# d_counter.net
KiCad netlist of a schematic drawn in EAGLE
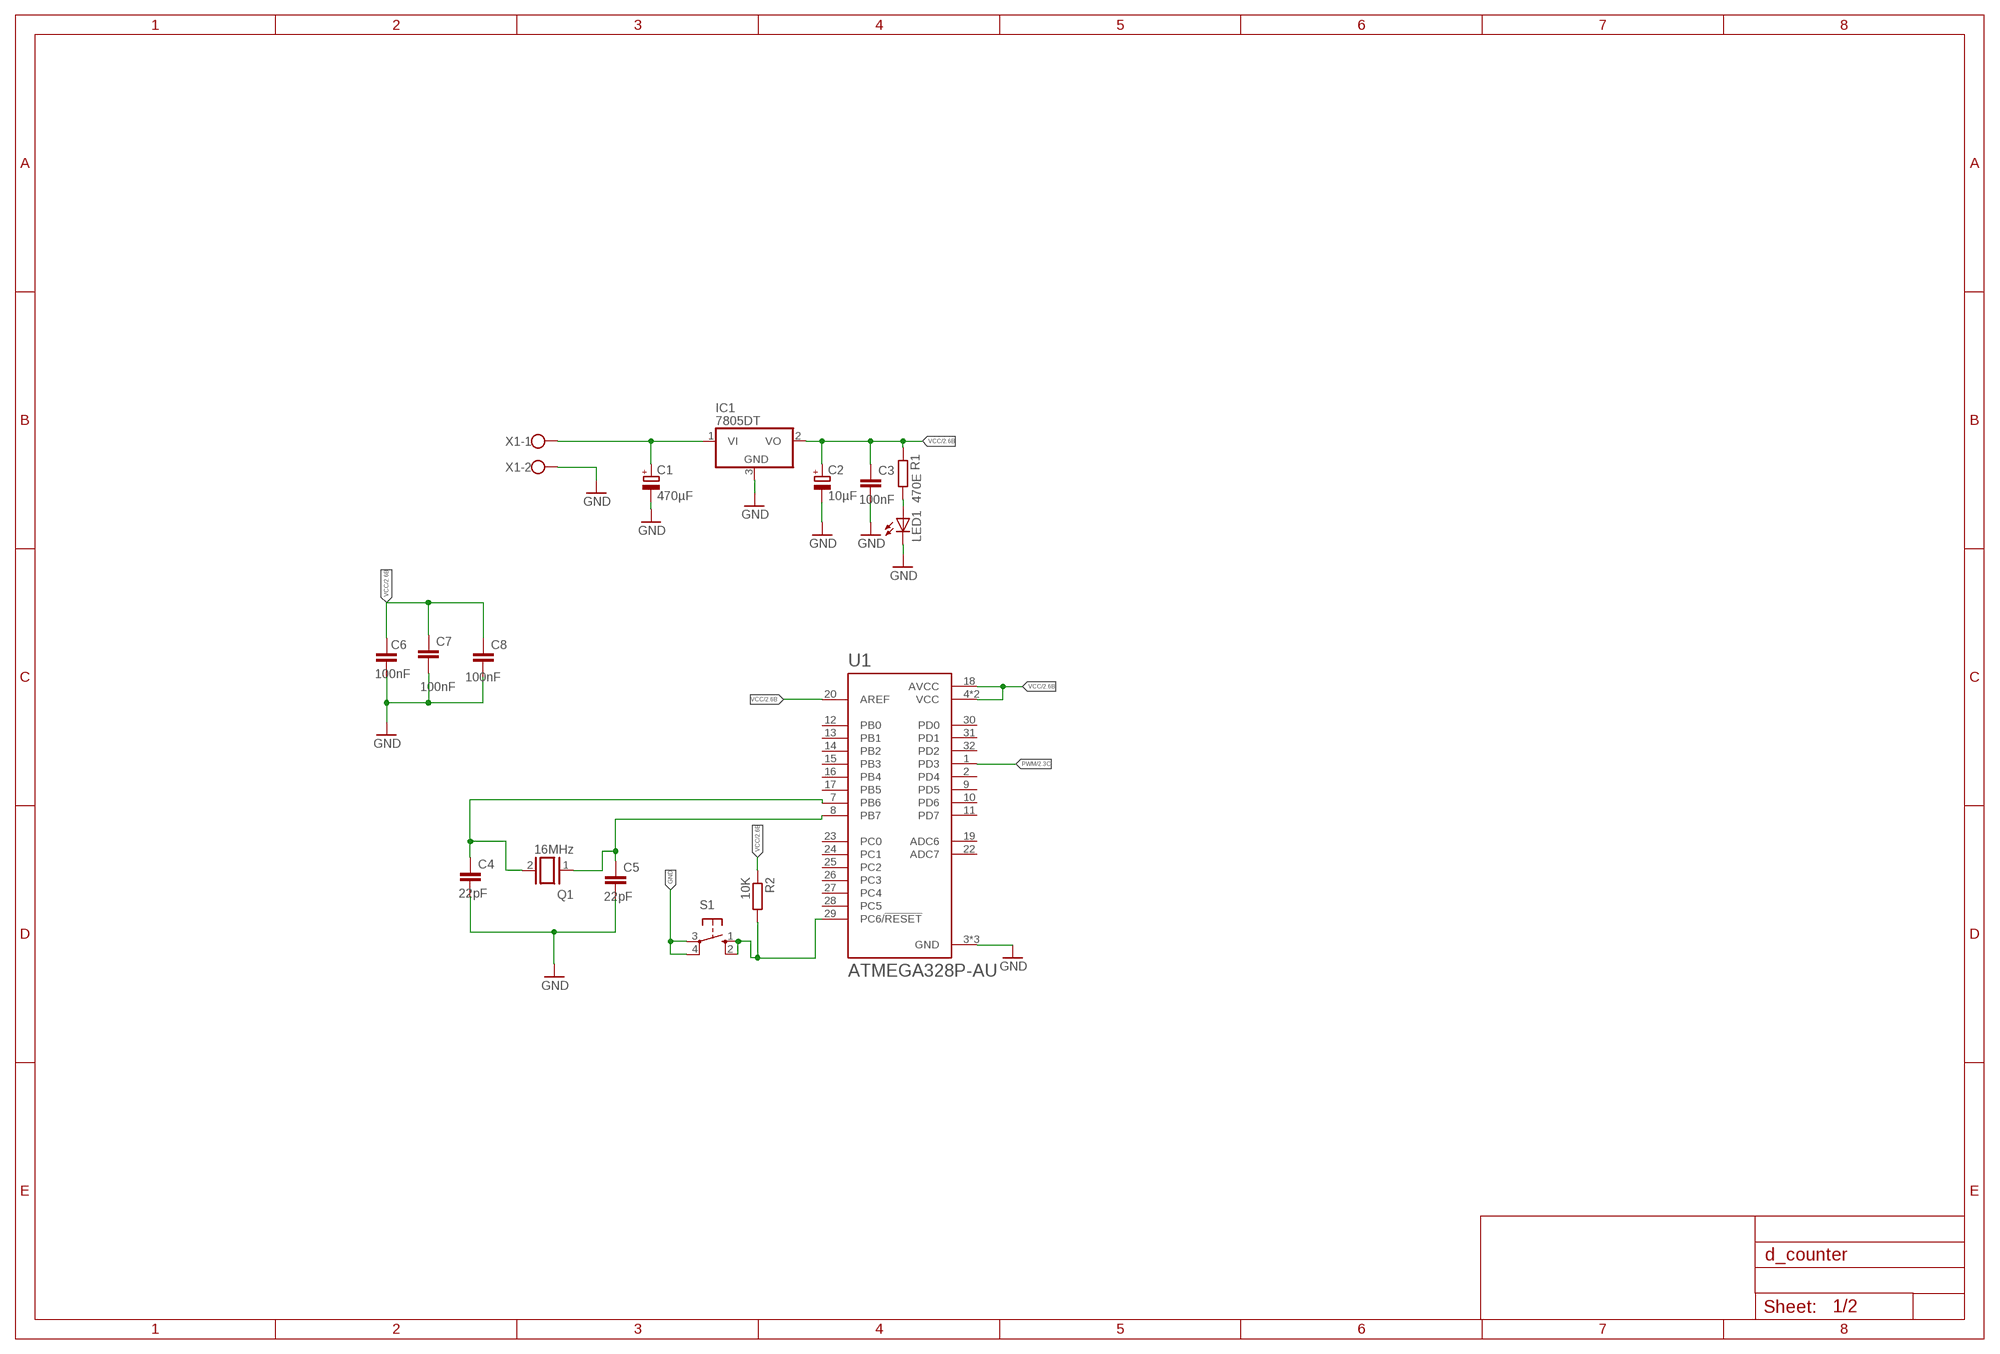
[diagram p0: schematic, sheet 1]
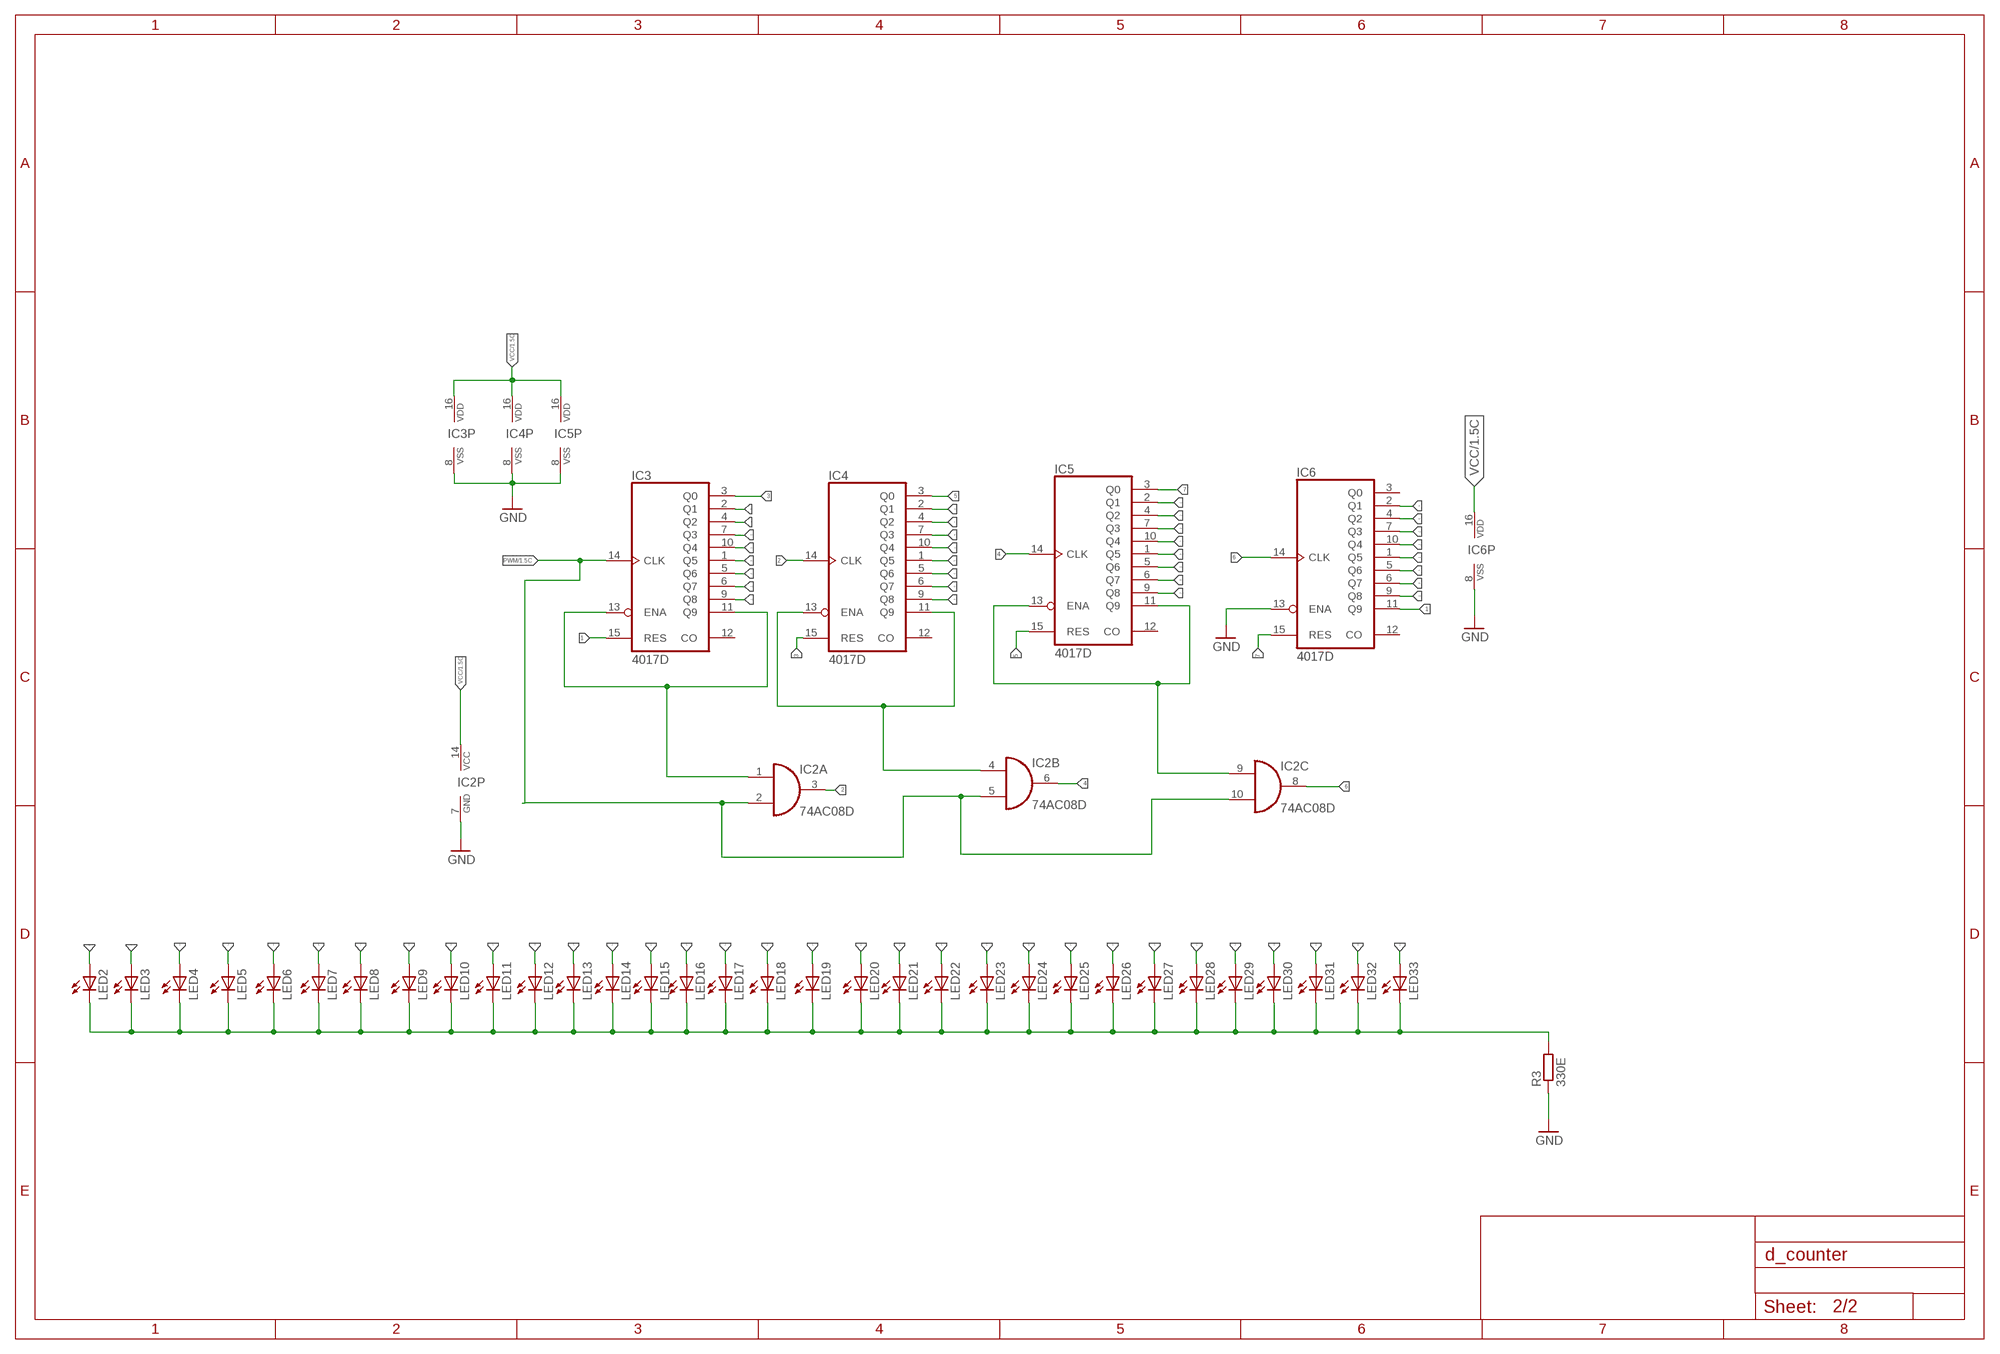
[diagram p1: schematic, sheet 2]

(export (version "E")
  (design (tool "Eeschema 10.0.6"))
  (components
    (comp (ref "IC2")
      (value "74AC08D")
      (footprint "eagle-import:SO14")
      (libsource (lib "eagle-import") (part "7408DAC"))
    )
    (comp (ref "IC3")
      (value "4017D")
      (footprint "eagle-import:SO16")
      (libsource (lib "eagle-import") (part "4017D"))
    )
    (comp (ref "IC4")
      (value "4017D")
      (footprint "eagle-import:SO16")
      (libsource (lib "eagle-import") (part "4017D"))
    )
    (comp (ref "IC5")
      (value "4017D")
      (footprint "eagle-import:SO16")
      (libsource (lib "eagle-import") (part "4017D"))
    )
    (comp (ref "IC6")
      (value "4017D")
      (footprint "eagle-import:SO16")
      (libsource (lib "eagle-import") (part "4017D"))
    )
    (comp (ref "LED2")
      (value "LEDSML1206")
      (footprint "eagle-import:SML1206")
      (libsource (lib "eagle-import") (part "LEDSML1206"))
    )
    (comp (ref "LED3")
      (value "LEDSML1206")
      (footprint "eagle-import:SML1206")
      (libsource (lib "eagle-import") (part "LEDSML1206"))
    )
    (comp (ref "LED4")
      (value "LEDSML1206")
      (footprint "eagle-import:SML1206")
      (libsource (lib "eagle-import") (part "LEDSML1206"))
    )
    (comp (ref "LED5")
      (value "LEDSML1206")
      (footprint "eagle-import:SML1206")
      (libsource (lib "eagle-import") (part "LEDSML1206"))
    )
    (comp (ref "LED6")
      (value "LEDSML1206")
      (footprint "eagle-import:SML1206")
      (libsource (lib "eagle-import") (part "LEDSML1206"))
    )
    (comp (ref "LED7")
      (value "LEDSML1206")
      (footprint "eagle-import:SML1206")
      (libsource (lib "eagle-import") (part "LEDSML1206"))
    )
    (comp (ref "LED8")
      (value "LEDSML1206")
      (footprint "eagle-import:SML1206")
      (libsource (lib "eagle-import") (part "LEDSML1206"))
    )
    (comp (ref "LED9")
      (value "LEDSML1206")
      (footprint "eagle-import:SML1206")
      (libsource (lib "eagle-import") (part "LEDSML1206"))
    )
    (comp (ref "LED10")
      (value "LEDSML1206")
      (footprint "eagle-import:SML1206")
      (libsource (lib "eagle-import") (part "LEDSML1206"))
    )
    (comp (ref "LED11")
      (value "LEDSML1206")
      (footprint "eagle-import:SML1206")
      (libsource (lib "eagle-import") (part "LEDSML1206"))
    )
    (comp (ref "LED12")
      (value "LEDSML1206")
      (footprint "eagle-import:SML1206")
      (libsource (lib "eagle-import") (part "LEDSML1206"))
    )
    (comp (ref "LED13")
      (value "LEDSML1206")
      (footprint "eagle-import:SML1206")
      (libsource (lib "eagle-import") (part "LEDSML1206"))
    )
    (comp (ref "LED14")
      (value "LEDSML1206")
      (footprint "eagle-import:SML1206")
      (libsource (lib "eagle-import") (part "LEDSML1206"))
    )
    (comp (ref "LED15")
      (value "LEDSML1206")
      (footprint "eagle-import:SML1206")
      (libsource (lib "eagle-import") (part "LEDSML1206"))
    )
    (comp (ref "LED16")
      (value "LEDSML1206")
      (footprint "eagle-import:SML1206")
      (libsource (lib "eagle-import") (part "LEDSML1206"))
    )
    (comp (ref "LED17")
      (value "LEDSML1206")
      (footprint "eagle-import:SML1206")
      (libsource (lib "eagle-import") (part "LEDSML1206"))
    )
    (comp (ref "LED18")
      (value "LEDSML1206")
      (footprint "eagle-import:SML1206")
      (libsource (lib "eagle-import") (part "LEDSML1206"))
    )
    (comp (ref "LED19")
      (value "LEDSML1206")
      (footprint "eagle-import:SML1206")
      (libsource (lib "eagle-import") (part "LEDSML1206"))
    )
    (comp (ref "LED20")
      (value "LEDSML1206")
      (footprint "eagle-import:SML1206")
      (libsource (lib "eagle-import") (part "LEDSML1206"))
    )
    (comp (ref "LED21")
      (value "LEDSML1206")
      (footprint "eagle-import:SML1206")
      (libsource (lib "eagle-import") (part "LEDSML1206"))
    )
    (comp (ref "LED22")
      (value "LEDSML1206")
      (footprint "eagle-import:SML1206")
      (libsource (lib "eagle-import") (part "LEDSML1206"))
    )
    (comp (ref "LED23")
      (value "LEDSML1206")
      (footprint "eagle-import:SML1206")
      (libsource (lib "eagle-import") (part "LEDSML1206"))
    )
    (comp (ref "LED24")
      (value "LEDSML1206")
      (footprint "eagle-import:SML1206")
      (libsource (lib "eagle-import") (part "LEDSML1206"))
    )
    (comp (ref "LED25")
      (value "LEDSML1206")
      (footprint "eagle-import:SML1206")
      (libsource (lib "eagle-import") (part "LEDSML1206"))
    )
    (comp (ref "LED26")
      (value "LEDSML1206")
      (footprint "eagle-import:SML1206")
      (libsource (lib "eagle-import") (part "LEDSML1206"))
    )
    (comp (ref "LED27")
      (value "LEDSML1206")
      (footprint "eagle-import:SML1206")
      (libsource (lib "eagle-import") (part "LEDSML1206"))
    )
    (comp (ref "LED28")
      (value "LEDSML1206")
      (footprint "eagle-import:SML1206")
      (libsource (lib "eagle-import") (part "LEDSML1206"))
    )
    (comp (ref "LED29")
      (value "LEDSML1206")
      (footprint "eagle-import:SML1206")
      (libsource (lib "eagle-import") (part "LEDSML1206"))
    )
    (comp (ref "LED30")
      (value "LEDSML1206")
      (footprint "eagle-import:SML1206")
      (libsource (lib "eagle-import") (part "LEDSML1206"))
    )
    (comp (ref "LED31")
      (value "LEDSML1206")
      (footprint "eagle-import:SML1206")
      (libsource (lib "eagle-import") (part "LEDSML1206"))
    )
    (comp (ref "LED32")
      (value "LEDSML1206")
      (footprint "eagle-import:SML1206")
      (libsource (lib "eagle-import") (part "LEDSML1206"))
    )
    (comp (ref "LED33")
      (value "LEDSML1206")
      (footprint "eagle-import:SML1206")
      (libsource (lib "eagle-import") (part "LEDSML1206"))
    )
    (comp (ref "R3")
      (value "330E")
      (footprint "eagle-import:R1206")
      (libsource (lib "eagle-import") (part "R-EU_R1206"))
    )
    (comp (ref "C1")
      (value "470µF")
      (footprint "eagle-import:150CLZ-1010")
      (libsource (lib "eagle-import") (part "CPOL-EU150CLZ-1010"))
    )
    (comp (ref "C2")
      (value "10µF")
      (footprint "eagle-import:150CLZ-1010")
      (libsource (lib "eagle-import") (part "CPOL-EU150CLZ-1010"))
    )
    (comp (ref "C3")
      (value "100nF")
      (footprint "eagle-import:C1206")
      (libsource (lib "eagle-import") (part "C-EUC1206"))
    )
    (comp (ref "C4")
      (value "22pF")
      (footprint "eagle-import:C1206")
      (libsource (lib "eagle-import") (part "C-EUC1206"))
    )
    (comp (ref "C5")
      (value "22pF")
      (footprint "eagle-import:C1206")
      (libsource (lib "eagle-import") (part "C-EUC1206"))
    )
    (comp (ref "C6")
      (value "100nF")
      (footprint "eagle-import:C1206")
      (libsource (lib "eagle-import") (part "C-EUC1206"))
    )
    (comp (ref "C7")
      (value "100nF")
      (footprint "eagle-import:C1206")
      (libsource (lib "eagle-import") (part "C-EUC1206"))
    )
    (comp (ref "C8")
      (value "100nF")
      (footprint "eagle-import:C1206")
      (libsource (lib "eagle-import") (part "C-EUC1206"))
    )
    (comp (ref "IC1")
      (value "7805DT")
      (footprint "eagle-import:TO252")
      (libsource (lib "eagle-import") (part "78DT05"))
    )
    (comp (ref "LED1")
      (value "LEDSMT1206")
      (footprint "eagle-import:1206")
      (libsource (lib "eagle-import") (part "LEDSMT1206"))
    )
    (comp (ref "Q1")
      (value "16MHz")
      (footprint "eagle-import:QS")
      (libsource (lib "eagle-import") (part "XTAL/S"))
    )
    (comp (ref "R1")
      (value "470E")
      (footprint "eagle-import:M1206")
      (libsource (lib "eagle-import") (part "resistor_R-EU_M1206"))
    )
    (comp (ref "R2")
      (value "10K")
      (footprint "eagle-import:R1206")
      (libsource (lib "eagle-import") (part "R-EU_R1206"))
    )
    (comp (ref "S1")
      (value "10-XX")
      (footprint "eagle-import:B3F-10XX")
      (fields (field (name "MPN") "B3F-1000"))
      (libsource (lib "eagle-import") (part "10-XX"))
    )
    (comp (ref "U1")
      (value "ATMEGA328P-AU")
      (footprint "eagle-import:QFP80P900X900X120-32N")
      (fields (field (name "MF") "Microchip"))
      (libsource (lib "eagle-import") (part "ATMEGA328P-AU"))
    )
    (comp (ref "X1")
      (value "W237-102")
      (footprint "eagle-import:W237-102")
      (fields (field (name "MPN") "237-102"))
      (libsource (lib "eagle-import") (part "W237-102"))
    )
  )
  (nets
    (net (code "1") (name "1") (class "Default")
      (node (ref "IC3") (pin "15") (pinfunction "RES_15") (pintype "input"))
      (node (ref "IC6") (pin "11") (pinfunction "Q9_11") (pintype "output"))
    )
    (net (code "2") (name "2") (class "Default")
      (node (ref "IC2") (pin "3") (pinfunction "O_3") (pintype "output"))
      (node (ref "IC4") (pin "14") (pinfunction "CLK_14") (pintype "input"))
    )
    (net (code "3") (name "3") (class "Default")
      (node (ref "IC3") (pin "3") (pinfunction "Q0_3") (pintype "output"))
      (node (ref "IC4") (pin "15") (pinfunction "RES_15") (pintype "input"))
    )
    (net (code "4") (name "4") (class "Default")
      (node (ref "IC2") (pin "6") (pinfunction "O_6") (pintype "output"))
      (node (ref "IC5") (pin "14") (pinfunction "CLK_14") (pintype "input"))
    )
    (net (code "5") (name "5") (class "Default")
      (node (ref "IC4") (pin "3") (pinfunction "Q0_3") (pintype "output"))
      (node (ref "IC5") (pin "15") (pinfunction "RES_15") (pintype "input"))
    )
    (net (code "6") (name "6") (class "Default")
      (node (ref "IC2") (pin "8") (pinfunction "O_8") (pintype "output"))
      (node (ref "IC6") (pin "14") (pinfunction "CLK_14") (pintype "input"))
    )
    (net (code "7") (name "7") (class "Default")
      (node (ref "IC5") (pin "3") (pinfunction "Q0_3") (pintype "output"))
      (node (ref "IC6") (pin "15") (pinfunction "RES_15") (pintype "input"))
    )
    (net (code "8") (name "8") (class "Default")
      (node (ref "IC3") (pin "2") (pinfunction "Q1_2") (pintype "output"))
      (node (ref "LED2") (pin "A") (pinfunction "A_A") (pintype "passive"))
    )
    (net (code "9") (name "9") (class "Default")
      (node (ref "IC3") (pin "4") (pinfunction "Q2_4") (pintype "output"))
      (node (ref "LED3") (pin "A") (pinfunction "A_A") (pintype "passive"))
    )
    (net (code "10") (name "10") (class "Default")
      (node (ref "IC3") (pin "7") (pinfunction "Q3_7") (pintype "output"))
      (node (ref "LED4") (pin "A") (pinfunction "A_A") (pintype "passive"))
    )
    (net (code "11") (name "11") (class "Default")
      (node (ref "IC3") (pin "10") (pinfunction "Q4_10") (pintype "output"))
      (node (ref "LED5") (pin "A") (pinfunction "A_A") (pintype "passive"))
    )
    (net (code "12") (name "12") (class "Default")
      (node (ref "IC3") (pin "1") (pinfunction "Q5_1") (pintype "output"))
      (node (ref "LED6") (pin "A") (pinfunction "A_A") (pintype "passive"))
    )
    (net (code "13") (name "13") (class "Default")
      (node (ref "IC3") (pin "5") (pinfunction "Q6_5") (pintype "output"))
      (node (ref "LED7") (pin "A") (pinfunction "A_A") (pintype "passive"))
    )
    (net (code "14") (name "14") (class "Default")
      (node (ref "IC3") (pin "6") (pinfunction "Q7_6") (pintype "output"))
      (node (ref "LED8") (pin "A") (pinfunction "A_A") (pintype "passive"))
    )
    (net (code "15") (name "15") (class "Default")
      (node (ref "IC3") (pin "9") (pinfunction "Q8_9") (pintype "output"))
      (node (ref "LED9") (pin "A") (pinfunction "A_A") (pintype "passive"))
    )
    (net (code "16") (name "16") (class "Default")
      (node (ref "IC4") (pin "2") (pinfunction "Q1_2") (pintype "output"))
      (node (ref "LED10") (pin "A") (pinfunction "A_A") (pintype "passive"))
    )
    (net (code "17") (name "17") (class "Default")
      (node (ref "IC4") (pin "4") (pinfunction "Q2_4") (pintype "output"))
      (node (ref "LED11") (pin "A") (pinfunction "A_A") (pintype "passive"))
    )
    (net (code "18") (name "18") (class "Default")
      (node (ref "IC4") (pin "7") (pinfunction "Q3_7") (pintype "output"))
      (node (ref "LED12") (pin "A") (pinfunction "A_A") (pintype "passive"))
    )
    (net (code "19") (name "19") (class "Default")
      (node (ref "IC4") (pin "10") (pinfunction "Q4_10") (pintype "output"))
      (node (ref "LED13") (pin "A") (pinfunction "A_A") (pintype "passive"))
    )
    (net (code "20") (name "20") (class "Default")
      (node (ref "IC4") (pin "1") (pinfunction "Q5_1") (pintype "output"))
      (node (ref "LED14") (pin "A") (pinfunction "A_A") (pintype "passive"))
    )
    (net (code "21") (name "21") (class "Default")
      (node (ref "IC4") (pin "5") (pinfunction "Q6_5") (pintype "output"))
      (node (ref "LED15") (pin "A") (pinfunction "A_A") (pintype "passive"))
    )
    (net (code "22") (name "22") (class "Default")
      (node (ref "IC4") (pin "6") (pinfunction "Q7_6") (pintype "output"))
      (node (ref "LED16") (pin "A") (pinfunction "A_A") (pintype "passive"))
    )
    (net (code "23") (name "23") (class "Default")
      (node (ref "IC4") (pin "9") (pinfunction "Q8_9") (pintype "output"))
      (node (ref "LED17") (pin "A") (pinfunction "A_A") (pintype "passive"))
    )
    (net (code "24") (name "24") (class "Default")
      (node (ref "IC5") (pin "2") (pinfunction "Q1_2") (pintype "output"))
      (node (ref "LED18") (pin "A") (pinfunction "A_A") (pintype "passive"))
    )
    (net (code "25") (name "25") (class "Default")
      (node (ref "IC5") (pin "4") (pinfunction "Q2_4") (pintype "output"))
      (node (ref "LED19") (pin "A") (pinfunction "A_A") (pintype "passive"))
    )
    (net (code "26") (name "26") (class "Default")
      (node (ref "IC5") (pin "7") (pinfunction "Q3_7") (pintype "output"))
      (node (ref "LED20") (pin "A") (pinfunction "A_A") (pintype "passive"))
    )
    (net (code "27") (name "27") (class "Default")
      (node (ref "IC5") (pin "10") (pinfunction "Q4_10") (pintype "output"))
      (node (ref "LED21") (pin "A") (pinfunction "A_A") (pintype "passive"))
    )
    (net (code "28") (name "28") (class "Default")
      (node (ref "IC5") (pin "1") (pinfunction "Q5_1") (pintype "output"))
      (node (ref "LED22") (pin "A") (pinfunction "A_A") (pintype "passive"))
    )
    (net (code "29") (name "29") (class "Default")
      (node (ref "IC5") (pin "5") (pinfunction "Q6_5") (pintype "output"))
      (node (ref "LED23") (pin "A") (pinfunction "A_A") (pintype "passive"))
    )
    (net (code "30") (name "30") (class "Default")
      (node (ref "IC5") (pin "6") (pinfunction "Q7_6") (pintype "output"))
      (node (ref "LED24") (pin "A") (pinfunction "A_A") (pintype "passive"))
    )
    (net (code "31") (name "31") (class "Default")
      (node (ref "IC5") (pin "9") (pinfunction "Q8_9") (pintype "output"))
      (node (ref "LED25") (pin "A") (pinfunction "A_A") (pintype "passive"))
    )
    (net (code "32") (name "32") (class "Default")
      (node (ref "IC6") (pin "2") (pinfunction "Q1_2") (pintype "output"))
      (node (ref "LED26") (pin "A") (pinfunction "A_A") (pintype "passive"))
    )
    (net (code "33") (name "33") (class "Default")
      (node (ref "IC6") (pin "4") (pinfunction "Q2_4") (pintype "output"))
      (node (ref "LED27") (pin "A") (pinfunction "A_A") (pintype "passive"))
    )
    (net (code "34") (name "34") (class "Default")
      (node (ref "IC6") (pin "7") (pinfunction "Q3_7") (pintype "output"))
      (node (ref "LED28") (pin "A") (pinfunction "A_A") (pintype "passive"))
    )
    (net (code "35") (name "35") (class "Default")
      (node (ref "IC6") (pin "10") (pinfunction "Q4_10") (pintype "output"))
      (node (ref "LED29") (pin "A") (pinfunction "A_A") (pintype "passive"))
    )
    (net (code "36") (name "36") (class "Default")
      (node (ref "IC6") (pin "1") (pinfunction "Q5_1") (pintype "output"))
      (node (ref "LED30") (pin "A") (pinfunction "A_A") (pintype "passive"))
    )
    (net (code "37") (name "37") (class "Default")
      (node (ref "IC6") (pin "5") (pinfunction "Q6_5") (pintype "output"))
      (node (ref "LED31") (pin "A") (pinfunction "A_A") (pintype "passive"))
    )
    (net (code "38") (name "38") (class "Default")
      (node (ref "IC6") (pin "6") (pinfunction "Q7_6") (pintype "output"))
      (node (ref "LED32") (pin "A") (pinfunction "A_A") (pintype "passive"))
    )
    (net (code "39") (name "39") (class "Default")
      (node (ref "IC6") (pin "9") (pinfunction "Q8_9") (pintype "output"))
      (node (ref "LED33") (pin "A") (pinfunction "A_A") (pintype "passive"))
    )
    (net (code "40") (name "GND") (class "Default")
      (node (ref "C1") (pin "-") (pinfunction "-_-") (pintype "passive"))
      (node (ref "C2") (pin "-") (pinfunction "-_-") (pintype "passive"))
      (node (ref "C3") (pin "2") (pinfunction "2_2") (pintype "passive"))
      (node (ref "C4") (pin "2") (pinfunction "2_2") (pintype "passive"))
      (node (ref "C5") (pin "2") (pinfunction "2_2") (pintype "passive"))
      (node (ref "C6") (pin "2") (pinfunction "2_2") (pintype "passive"))
      (node (ref "C7") (pin "2") (pinfunction "2_2") (pintype "passive"))
      (node (ref "C8") (pin "2") (pinfunction "2_2") (pintype "passive"))
      (node (ref "IC1") (pin "3") (pinfunction "GND_3") (pintype "passive"))
      (node (ref "IC2") (pin "7") (pinfunction "GND_7") (pintype "power_in"))
      (node (ref "IC3") (pin "8") (pinfunction "VSS_8") (pintype "power_in"))
      (node (ref "IC4") (pin "8") (pinfunction "VSS_8") (pintype "power_in"))
      (node (ref "IC5") (pin "8") (pinfunction "VSS_8") (pintype "power_in"))
      (node (ref "IC6") (pin "13") (pinfunction "ENA_13") (pintype "input"))
      (node (ref "IC6") (pin "8") (pinfunction "VSS_8") (pintype "power_in"))
      (node (ref "LED1") (pin "C") (pinfunction "C_C") (pintype "passive"))
      (node (ref "R3") (pin "1") (pinfunction "1_1") (pintype "passive"))
      (node (ref "S1") (pin "3") (pinfunction "P_3") (pintype "passive"))
      (node (ref "S1") (pin "4") (pinfunction "P1_4") (pintype "passive"))
      (node (ref "U1") (pin "21") (pinfunction "GND_21") (pintype "power_in"))
      (node (ref "U1") (pin "3") (pinfunction "GND_3") (pintype "power_in"))
      (node (ref "U1") (pin "5") (pinfunction "GND_5") (pintype "power_in"))
      (node (ref "X1") (pin "2") (pinfunction "KL_2") (pintype "passive"))
    )
    (net (code "41") (name "Net-(IC1-VI)") (class "Default")
      (node (ref "C1") (pin "+") (pinfunction "+_+") (pintype "passive"))
      (node (ref "IC1") (pin "1") (pinfunction "VI_1") (pintype "input"))
      (node (ref "X1") (pin "1") (pinfunction "KL_1") (pintype "passive"))
    )
    (net (code "42") (name "Net-(IC2A-I0)") (class "Default")
      (node (ref "IC2") (pin "1") (pinfunction "I0_1") (pintype "input"))
      (node (ref "IC3") (pin "11") (pinfunction "Q9_11") (pintype "output"))
      (node (ref "IC3") (pin "13") (pinfunction "ENA_13") (pintype "input"))
    )
    (net (code "43") (name "Net-(IC2B-I0)") (class "Default")
      (node (ref "IC2") (pin "4") (pinfunction "I0_4") (pintype "input"))
      (node (ref "IC4") (pin "11") (pinfunction "Q9_11") (pintype "output"))
      (node (ref "IC4") (pin "13") (pinfunction "ENA_13") (pintype "input"))
    )
    (net (code "44") (name "Net-(IC2C-I0)") (class "Default")
      (node (ref "IC2") (pin "9") (pinfunction "I0_9") (pintype "input"))
      (node (ref "IC5") (pin "11") (pinfunction "Q9_11") (pintype "output"))
      (node (ref "IC5") (pin "13") (pinfunction "ENA_13") (pintype "input"))
    )
    (net (code "45") (name "Net-(LED1-PadA)") (class "Default")
      (node (ref "LED1") (pin "A") (pinfunction "A_A") (pintype "passive"))
      (node (ref "R1") (pin "2") (pinfunction "2_2") (pintype "passive"))
    )
    (net (code "46") (name "Net-(LED10-PadC)") (class "Default")
      (node (ref "LED10") (pin "C") (pinfunction "C_C") (pintype "passive"))
      (node (ref "LED11") (pin "C") (pinfunction "C_C") (pintype "passive"))
      (node (ref "LED12") (pin "C") (pinfunction "C_C") (pintype "passive"))
      (node (ref "LED13") (pin "C") (pinfunction "C_C") (pintype "passive"))
      (node (ref "LED14") (pin "C") (pinfunction "C_C") (pintype "passive"))
      (node (ref "LED15") (pin "C") (pinfunction "C_C") (pintype "passive"))
      (node (ref "LED16") (pin "C") (pinfunction "C_C") (pintype "passive"))
      (node (ref "LED17") (pin "C") (pinfunction "C_C") (pintype "passive"))
      (node (ref "LED18") (pin "C") (pinfunction "C_C") (pintype "passive"))
      (node (ref "LED19") (pin "C") (pinfunction "C_C") (pintype "passive"))
      (node (ref "LED2") (pin "C") (pinfunction "C_C") (pintype "passive"))
      (node (ref "LED20") (pin "C") (pinfunction "C_C") (pintype "passive"))
      (node (ref "LED21") (pin "C") (pinfunction "C_C") (pintype "passive"))
      (node (ref "LED22") (pin "C") (pinfunction "C_C") (pintype "passive"))
      (node (ref "LED23") (pin "C") (pinfunction "C_C") (pintype "passive"))
      (node (ref "LED24") (pin "C") (pinfunction "C_C") (pintype "passive"))
      (node (ref "LED25") (pin "C") (pinfunction "C_C") (pintype "passive"))
      (node (ref "LED26") (pin "C") (pinfunction "C_C") (pintype "passive"))
      (node (ref "LED27") (pin "C") (pinfunction "C_C") (pintype "passive"))
      (node (ref "LED28") (pin "C") (pinfunction "C_C") (pintype "passive"))
      (node (ref "LED29") (pin "C") (pinfunction "C_C") (pintype "passive"))
      (node (ref "LED3") (pin "C") (pinfunction "C_C") (pintype "passive"))
      (node (ref "LED30") (pin "C") (pinfunction "C_C") (pintype "passive"))
      (node (ref "LED31") (pin "C") (pinfunction "C_C") (pintype "passive"))
      (node (ref "LED32") (pin "C") (pinfunction "C_C") (pintype "passive"))
      (node (ref "LED33") (pin "C") (pinfunction "C_C") (pintype "passive"))
      (node (ref "LED4") (pin "C") (pinfunction "C_C") (pintype "passive"))
      (node (ref "LED5") (pin "C") (pinfunction "C_C") (pintype "passive"))
      (node (ref "LED6") (pin "C") (pinfunction "C_C") (pintype "passive"))
      (node (ref "LED7") (pin "C") (pinfunction "C_C") (pintype "passive"))
      (node (ref "LED8") (pin "C") (pinfunction "C_C") (pintype "passive"))
      (node (ref "LED9") (pin "C") (pinfunction "C_C") (pintype "passive"))
      (node (ref "R3") (pin "2") (pinfunction "2_2") (pintype "passive"))
    )
    (net (code "47") (name "Net-(S1-S)") (class "Default")
      (node (ref "R2") (pin "2") (pinfunction "2_2") (pintype "passive"))
      (node (ref "S1") (pin "1") (pinfunction "S_1") (pintype "passive"))
      (node (ref "S1") (pin "2") (pinfunction "S1_2") (pintype "passive"))
      (node (ref "U1") (pin "29") (pinfunction "PC6/~{RESET}_29") (pintype "bidirectional"))
    )
    (net (code "48") (name "Net-(U1-PB6)") (class "Default")
      (node (ref "C4") (pin "1") (pinfunction "1_1") (pintype "passive"))
      (node (ref "Q1") (pin "2") (pinfunction "2_2") (pintype "passive"))
      (node (ref "U1") (pin "7") (pinfunction "PB6_7") (pintype "bidirectional"))
    )
    (net (code "49") (name "Net-(U1-PB7)") (class "Default")
      (node (ref "C5") (pin "1") (pinfunction "1_1") (pintype "passive"))
      (node (ref "Q1") (pin "1") (pinfunction "1_1") (pintype "passive"))
      (node (ref "U1") (pin "8") (pinfunction "PB7_8") (pintype "bidirectional"))
    )
    (net (code "50") (name "PWM") (class "Default")
      (node (ref "IC2") (pin "10") (pinfunction "I1_10") (pintype "input"))
      (node (ref "IC2") (pin "2") (pinfunction "I1_2") (pintype "input"))
      (node (ref "IC2") (pin "5") (pinfunction "I1_5") (pintype "input"))
      (node (ref "IC3") (pin "14") (pinfunction "CLK_14") (pintype "input"))
      (node (ref "U1") (pin "1") (pinfunction "PD3_1") (pintype "bidirectional"))
    )
    (net (code "51") (name "VCC") (class "Default")
      (node (ref "C2") (pin "+") (pinfunction "+_+") (pintype "passive"))
      (node (ref "C3") (pin "1") (pinfunction "1_1") (pintype "passive"))
      (node (ref "C6") (pin "1") (pinfunction "1_1") (pintype "passive"))
      (node (ref "C7") (pin "1") (pinfunction "1_1") (pintype "passive"))
      (node (ref "C8") (pin "1") (pinfunction "1_1") (pintype "passive"))
      (node (ref "IC1") (pin "2") (pinfunction "VO_2") (pintype "passive"))
      (node (ref "IC2") (pin "14") (pinfunction "VCC_14") (pintype "power_in"))
      (node (ref "IC3") (pin "16") (pinfunction "VDD_16") (pintype "power_in"))
      (node (ref "IC4") (pin "16") (pinfunction "VDD_16") (pintype "power_in"))
      (node (ref "IC5") (pin "16") (pinfunction "VDD_16") (pintype "power_in"))
      (node (ref "IC6") (pin "16") (pinfunction "VDD_16") (pintype "power_in"))
      (node (ref "R1") (pin "1") (pinfunction "1_1") (pintype "passive"))
      (node (ref "R2") (pin "1") (pinfunction "1_1") (pintype "passive"))
      (node (ref "U1") (pin "18") (pinfunction "AVCC_18") (pintype "power_in"))
      (node (ref "U1") (pin "20") (pinfunction "AREF_20") (pintype "input"))
      (node (ref "U1") (pin "4") (pinfunction "VCC_4") (pintype "power_in"))
      (node (ref "U1") (pin "6") (pinfunction "VCC_6") (pintype "power_in"))
    )
    (net (code "52") (name "unconnected-(IC3A-CO-Pad12)") (class "Default")
      (node (ref "IC3") (pin "12") (pinfunction "CO_12") (pintype "output"))
    )
    (net (code "53") (name "unconnected-(IC4A-CO-Pad12)") (class "Default")
      (node (ref "IC4") (pin "12") (pinfunction "CO_12") (pintype "output"))
    )
    (net (code "54") (name "unconnected-(IC5A-CO-Pad12)") (class "Default")
      (node (ref "IC5") (pin "12") (pinfunction "CO_12") (pintype "output"))
    )
    (net (code "55") (name "unconnected-(IC6A-CO-Pad12)") (class "Default")
      (node (ref "IC6") (pin "12") (pinfunction "CO_12") (pintype "output"))
    )
    (net (code "56") (name "unconnected-(IC6A-Q0-Pad3)") (class "Default")
      (node (ref "IC6") (pin "3") (pinfunction "Q0_3") (pintype "output"))
    )
    (net (code "57") (name "unconnected-(U1-ADC6-Pad19)") (class "Default")
      (node (ref "U1") (pin "19") (pinfunction "ADC6_19") (pintype "bidirectional"))
    )
    (net (code "58") (name "unconnected-(U1-ADC7-Pad22)") (class "Default")
      (node (ref "U1") (pin "22") (pinfunction "ADC7_22") (pintype "bidirectional"))
    )
    (net (code "59") (name "unconnected-(U1-PB0-Pad12)") (class "Default")
      (node (ref "U1") (pin "12") (pinfunction "PB0_12") (pintype "bidirectional"))
    )
    (net (code "60") (name "unconnected-(U1-PB1-Pad13)") (class "Default")
      (node (ref "U1") (pin "13") (pinfunction "PB1_13") (pintype "bidirectional"))
    )
    (net (code "61") (name "unconnected-(U1-PB2-Pad14)") (class "Default")
      (node (ref "U1") (pin "14") (pinfunction "PB2_14") (pintype "bidirectional"))
    )
    (net (code "62") (name "unconnected-(U1-PB3-Pad15)") (class "Default")
      (node (ref "U1") (pin "15") (pinfunction "PB3_15") (pintype "bidirectional"))
    )
    (net (code "63") (name "unconnected-(U1-PB4-Pad16)") (class "Default")
      (node (ref "U1") (pin "16") (pinfunction "PB4_16") (pintype "bidirectional"))
    )
    (net (code "64") (name "unconnected-(U1-PB5-Pad17)") (class "Default")
      (node (ref "U1") (pin "17") (pinfunction "PB5_17") (pintype "bidirectional"))
    )
    (net (code "65") (name "unconnected-(U1-PC0-Pad23)") (class "Default")
      (node (ref "U1") (pin "23") (pinfunction "PC0_23") (pintype "bidirectional"))
    )
    (net (code "66") (name "unconnected-(U1-PC1-Pad24)") (class "Default")
      (node (ref "U1") (pin "24") (pinfunction "PC1_24") (pintype "bidirectional"))
    )
    (net (code "67") (name "unconnected-(U1-PC2-Pad25)") (class "Default")
      (node (ref "U1") (pin "25") (pinfunction "PC2_25") (pintype "bidirectional"))
    )
    (net (code "68") (name "unconnected-(U1-PC3-Pad26)") (class "Default")
      (node (ref "U1") (pin "26") (pinfunction "PC3_26") (pintype "bidirectional"))
    )
    (net (code "69") (name "unconnected-(U1-PC4-Pad27)") (class "Default")
      (node (ref "U1") (pin "27") (pinfunction "PC4_27") (pintype "bidirectional"))
    )
    (net (code "70") (name "unconnected-(U1-PC5-Pad28)") (class "Default")
      (node (ref "U1") (pin "28") (pinfunction "PC5_28") (pintype "bidirectional"))
    )
    (net (code "71") (name "unconnected-(U1-PD0-Pad30)") (class "Default")
      (node (ref "U1") (pin "30") (pinfunction "PD0_30") (pintype "bidirectional"))
    )
    (net (code "72") (name "unconnected-(U1-PD1-Pad31)") (class "Default")
      (node (ref "U1") (pin "31") (pinfunction "PD1_31") (pintype "bidirectional"))
    )
    (net (code "73") (name "unconnected-(U1-PD2-Pad32)") (class "Default")
      (node (ref "U1") (pin "32") (pinfunction "PD2_32") (pintype "bidirectional"))
    )
    (net (code "74") (name "unconnected-(U1-PD4-Pad2)") (class "Default")
      (node (ref "U1") (pin "2") (pinfunction "PD4_2") (pintype "bidirectional"))
    )
    (net (code "75") (name "unconnected-(U1-PD5-Pad9)") (class "Default")
      (node (ref "U1") (pin "9") (pinfunction "PD5_9") (pintype "bidirectional"))
    )
    (net (code "76") (name "unconnected-(U1-PD6-Pad10)") (class "Default")
      (node (ref "U1") (pin "10") (pinfunction "PD6_10") (pintype "bidirectional"))
    )
    (net (code "77") (name "unconnected-(U1-PD7-Pad11)") (class "Default")
      (node (ref "U1") (pin "11") (pinfunction "PD7_11") (pintype "bidirectional"))
    )
  )
)
